# LAN.net
KiCad netlist of a schematic drawn in Altium Designer
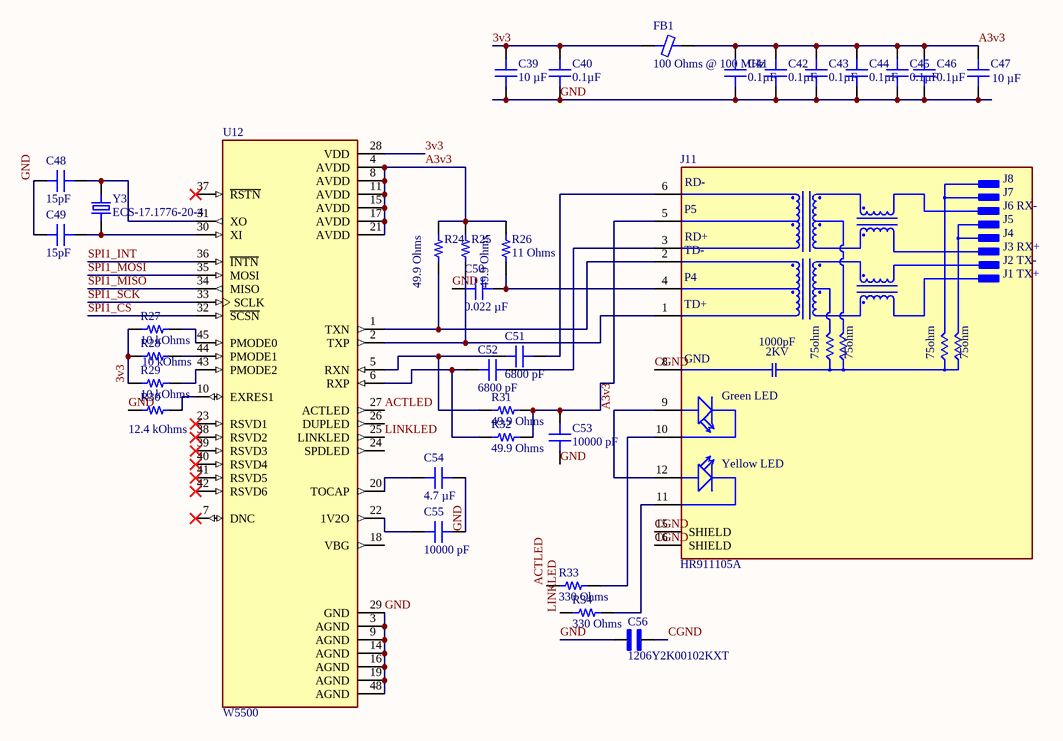
[diagram p0: LAN.SchDoc]

(export (version "E")
  (design (tool "Eeschema 10.0.6"))
  (components
    (comp (ref "C39")
      (value "10 µF")
      (footprint "CAP 1206_3216 - 0.8MM")
      (description "CAP CER 10UF 16V X5R 1206")
      (fields
        (field (name "PART NUMBER") "EMK316BJ106MD-T")
        (field (name "CAPACITANCE") "10 µF")
        (field (name "MANUFACTURER") "Taiyo Yuden")
      )
      (libsource (lib "Celestial Altium Library - altium_library") (part "Capacitor"))
    )
    (comp (ref "C40")
      (value "1µF")
      (footprint "CAP 0805_2012")
      (description "CAP CER 1UF 10V X7R 0805")
      (fields
        (field (name "PART NUMBER") "0805ZC105KAT4A")
        (field (name "CAPACITANCE") "0.1µF")
        (field (name "MANUFACTURER") "AVX Corporation")
      )
      (libsource (lib "Celestial Altium Library - altium_library") (part "Capacitor"))
    )
    (comp (ref "C41")
      (value "1µF")
      (footprint "CAP 0805_2012")
      (description "CAP CER 1UF 10V X7R 0805")
      (fields
        (field (name "PART NUMBER") "0805ZC105KAT4A")
        (field (name "CAPACITANCE") "0.1µF")
        (field (name "MANUFACTURER") "AVX Corporation")
      )
      (libsource (lib "Celestial Altium Library - altium_library") (part "Capacitor"))
    )
    (comp (ref "C42")
      (value "1µF")
      (footprint "CAP 0805_2012")
      (description "CAP CER 1UF 10V X7R 0805")
      (fields
        (field (name "PART NUMBER") "0805ZC105KAT4A")
        (field (name "CAPACITANCE") "0.1µF")
        (field (name "MANUFACTURER") "AVX Corporation")
      )
      (libsource (lib "Celestial Altium Library - altium_library") (part "Capacitor"))
    )
    (comp (ref "C43")
      (value "1µF")
      (footprint "CAP 0805_2012")
      (description "CAP CER 1UF 10V X7R 0805")
      (fields
        (field (name "PART NUMBER") "0805ZC105KAT4A")
        (field (name "CAPACITANCE") "0.1µF")
        (field (name "MANUFACTURER") "AVX Corporation")
      )
      (libsource (lib "Celestial Altium Library - altium_library") (part "Capacitor"))
    )
    (comp (ref "C44")
      (value "1µF")
      (footprint "CAP 0805_2012")
      (description "CAP CER 1UF 10V X7R 0805")
      (fields
        (field (name "PART NUMBER") "0805ZC105KAT4A")
        (field (name "CAPACITANCE") "0.1µF")
        (field (name "MANUFACTURER") "AVX Corporation")
      )
      (libsource (lib "Celestial Altium Library - altium_library") (part "Capacitor"))
    )
    (comp (ref "C45")
      (value "1µF")
      (footprint "CAP 0805_2012")
      (description "CAP CER 1UF 10V X7R 0805")
      (fields
        (field (name "PART NUMBER") "0805ZC105KAT4A")
        (field (name "CAPACITANCE") "0.1µF")
        (field (name "MANUFACTURER") "AVX Corporation")
      )
      (libsource (lib "Celestial Altium Library - altium_library") (part "Capacitor"))
    )
    (comp (ref "C46")
      (value "1µF")
      (footprint "CAP 0805_2012")
      (description "CAP CER 1UF 10V X7R 0805")
      (fields
        (field (name "PART NUMBER") "0805ZC105KAT4A")
        (field (name "CAPACITANCE") "0.1µF")
        (field (name "MANUFACTURER") "AVX Corporation")
      )
      (libsource (lib "Celestial Altium Library - altium_library") (part "Capacitor"))
    )
    (comp (ref "C47")
      (value "10 µF")
      (footprint "CAP 1206_3216 - 0.8MM")
      (description "CAP CER 10UF 16V X5R 1206")
      (fields
        (field (name "PART NUMBER") "EMK316BJ106MD-T")
        (field (name "CAPACITANCE") "10 µF")
        (field (name "MANUFACTURER") "Taiyo Yuden")
      )
      (libsource (lib "Celestial Altium Library - altium_library") (part "Capacitor"))
    )
    (comp (ref "C48")
      (value "15pF")
      (footprint "CAP 0805_2012")
      (description "CAP CER 15PF 50V C0G/NP0 0805")
      (fields
        (field (name "PART NUMBER") "08055A150JAT2A")
        (field (name "CAPACITANCE") "15pF")
        (field (name "MANUFACTURER") "AVX Corporation")
      )
      (libsource (lib "Celestial Altium Library - altium_library") (part "Capacitor"))
    )
    (comp (ref "C49")
      (value "15pF")
      (footprint "CAP 0805_2012")
      (description "CAP CER 15PF 50V C0G/NP0 0805")
      (fields
        (field (name "PART NUMBER") "08055A150JAT2A")
        (field (name "CAPACITANCE") "15pF")
        (field (name "MANUFACTURER") "AVX Corporation")
      )
      (libsource (lib "Celestial Altium Library - altium_library") (part "Capacitor"))
    )
    (comp (ref "C50")
      (value "0.022 µF")
      (footprint "CAP 0805_2012")
      (description "CAP CER 0805 22NF 50V X7R 10%")
      (fields
        (field (name "PART NUMBER") "C0805C223K5RECAUTO")
        (field (name "CAPACITANCE") "0.022 µF")
        (field (name "MANUFACTURER") "KEMET")
      )
      (libsource (lib "Celestial Altium Library - altium_library") (part "Capacitor"))
    )
    (comp (ref "C51")
      (value "6800 pF")
      (footprint "CAP 0805_2012")
      (description "CAP CER 0805 6.8NF 25V C0G 20%")
      (fields
        (field (name "PART NUMBER") "C0805C682M3GEC7800")
        (field (name "CAPACITANCE") "6800 pF")
        (field (name "MANUFACTURER") "KEMET")
      )
      (libsource (lib "Celestial Altium Library - altium_library") (part "Capacitor"))
    )
    (comp (ref "C52")
      (value "6800 pF")
      (footprint "CAP 0805_2012")
      (description "CAP CER 0805 6.8NF 25V C0G 20%")
      (fields
        (field (name "PART NUMBER") "C0805C682M3GEC7800")
        (field (name "CAPACITANCE") "6800 pF")
        (field (name "MANUFACTURER") "KEMET")
      )
      (libsource (lib "Celestial Altium Library - altium_library") (part "Capacitor"))
    )
    (comp (ref "C53")
      (value "10000 pF")
      (footprint "CAP 0805_2012")
      (description "CAP CER 0805 10NF 100V X7R")
      (fields
        (field (name "PART NUMBER") "C0805X103K1RAC3316")
        (field (name "CAPACITANCE") "10000 pF")
        (field (name "MANUFACTURER") "KEMET")
      )
      (libsource (lib "Celestial Altium Library - altium_library") (part "Capacitor"))
    )
    (comp (ref "C54")
      (value "4.7 µF")
      (footprint "CAP 0805_2012")
      (description "4.70UF 25.0V")
      (fields
        (field (name "PART NUMBER") "C0805X475M3RAC7800")
        (field (name "CAPACITANCE") "4.7 µF")
        (field (name "MANUFACTURER") "KEMET")
      )
      (libsource (lib "Celestial Altium Library - altium_library") (part "Capacitor"))
    )
    (comp (ref "C55")
      (value "10000 pF")
      (footprint "CAP 0805_2012")
      (description "CAP CER 0805 10NF 100V X7R")
      (fields
        (field (name "PART NUMBER") "C0805X103K1RAC3316")
        (field (name "CAPACITANCE") "10000 pF")
        (field (name "MANUFACTURER") "KEMET")
      )
      (libsource (lib "Celestial Altium Library - altium_library") (part "Capacitor"))
    )
    (comp (ref "C56")
      (value "1206Y2K00102KXT")
      (footprint "CAPC3216X160N")
      (description "1000 pF Â±10% 2000V (2kV) Ceramic Capacitor X7R 1206 (3216 Metric)")
      (fields (field (name "MF") "Knowles Syfer"))
      (libsource (lib "1206Y2K00102KXT") (part "1206Y2K00102KXT"))
    )
    (comp (ref "FB1")
      (value "100 Ohms @ 100 MHz")
      (footprint "FER 0805_2012")
      (description "FERRITE BEAD, CHIP, 0805, 100 OH")
      (fields (field (name "PART NUMBER") "HRB0805S101K1.00FT") (field (name "MANUFACTURER") "AEM, Inc."))
      (libsource (lib "Celestial Altium Library - altium_library") (part "Ferrite Chip"))
    )
    (comp (ref "J11")
      (value "HR911105A")
      (footprint "HANRUN_HR911105A")
      (description "DIP RJ45 Connector;")
      (fields (field (name "MF") "hanrun"))
      (libsource (lib "HR911105A") (part "HR911105A"))
    )
    (comp (ref "R24")
      (value "49.9 Ohms")
      (footprint "RES 0805_2012")
      (description "RCC0805 100 49R9 1% ET1 E3")
      (fields (field (name "PART NUMBER") "RCC080549R9FKEA") (field (name "MANUFACTURER") "Vishay Dale"))
      (libsource (lib "Celestial Altium Library - altium_library") (part "Resistor"))
    )
    (comp (ref "R25")
      (value "49.9 Ohms")
      (footprint "RES 0805_2012")
      (description "RCC0805 100 49R9 1% ET1 E3")
      (fields (field (name "PART NUMBER") "RCC080549R9FKEA") (field (name "MANUFACTURER") "Vishay Dale"))
      (libsource (lib "Celestial Altium Library - altium_library") (part "Resistor"))
    )
    (comp (ref "R26")
      (value "11 Ohms")
      (footprint "RES 0805_2012")
      (description "RES SMD 11 OHM 1% 1/8W 0805")
      (fields (field (name "PART NUMBER") "KTR10EZPF11R0") (field (name "MANUFACTURER") "Rohm Semiconductor"))
      (libsource (lib "Celestial Altium Library - altium_library") (part "Resistor"))
    )
    (comp (ref "R27")
      (value "10 kOhms")
      (footprint "RES 0805_2012")
      (description "RES 10K OHM 0.1% 1/10W 0805")
      (fields
        (field (name "PART NUMBER") "RNCS0805BKE10K0")
        (field (name "MANUFACTURER") "Stackpole Electronics Inc")
      )
      (libsource (lib "Celestial Altium Library - altium_library") (part "Resistor"))
    )
    (comp (ref "R28")
      (value "10 kOhms")
      (footprint "RES 0805_2012")
      (description "RES 10K OHM 0.1% 1/10W 0805")
      (fields
        (field (name "PART NUMBER") "RNCS0805BKE10K0")
        (field (name "MANUFACTURER") "Stackpole Electronics Inc")
      )
      (libsource (lib "Celestial Altium Library - altium_library") (part "Resistor"))
    )
    (comp (ref "R29")
      (value "10 kOhms")
      (footprint "RES 0805_2012")
      (description "RES 10K OHM 0.1% 1/10W 0805")
      (fields
        (field (name "PART NUMBER") "RNCS0805BKE10K0")
        (field (name "MANUFACTURER") "Stackpole Electronics Inc")
      )
      (libsource (lib "Celestial Altium Library - altium_library") (part "Resistor"))
    )
    (comp (ref "R30")
      (value "12.4 kOhms")
      (footprint "RES 0805_2012")
      (description "RES 12.4 KOHMS 0.1% 1/5W 0805")
      (fields
        (field (name "PART NUMBER") "RQ73C2A12K4BTD")
        (field (name "MANUFACTURER") "TE Connectivity Passive Product")
      )
      (libsource (lib "Celestial Altium Library - altium_library") (part "Resistor"))
    )
    (comp (ref "R31")
      (value "49.9 Ohms")
      (footprint "RES 0805_2012")
      (description "RCC0805 100 49R9 1% ET1 E3")
      (fields (field (name "PART NUMBER") "RCC080549R9FKEA") (field (name "MANUFACTURER") "Vishay Dale"))
      (libsource (lib "Celestial Altium Library - altium_library") (part "Resistor"))
    )
    (comp (ref "R32")
      (value "49.9 Ohms")
      (footprint "RES 0805_2012")
      (description "RCC0805 100 49R9 1% ET1 E3")
      (fields (field (name "PART NUMBER") "RCC080549R9FKEA") (field (name "MANUFACTURER") "Vishay Dale"))
      (libsource (lib "Celestial Altium Library - altium_library") (part "Resistor"))
    )
    (comp (ref "R33")
      (value "330 Ohms")
      (footprint "YAGEO RES 0805_2012")
      (description "RES 330 OHM 1% 1/8W 0805")
      (fields (field (name "PART NUMBER") "RC0805FR-07330RL") (field (name "MANUFACTURER") "Yageo"))
      (libsource (lib "Celestial Altium Library - altium_library") (part "Resistor"))
    )
    (comp (ref "R34")
      (value "330 Ohms")
      (footprint "YAGEO RES 0805_2012")
      (description "RES 330 OHM 1% 1/8W 0805")
      (fields (field (name "PART NUMBER") "RC0805FR-07330RL") (field (name "MANUFACTURER") "Yageo"))
      (libsource (lib "Celestial Altium Library - altium_library") (part "Resistor"))
    )
    (comp (ref "U12")
      (value "W5500")
      (footprint "QFP50P900X900X160-48N")
      (description "Hardwired TCP/IP embedded Ethernet controller")
      (libsource (lib "W5500") (part "W5500"))
    )
    (comp (ref "Y3")
      (value "ECS-17.1776-20-4")
      (footprint "XTAL_ECS-160-20-4X")
      (description "Crystals 17.1776MHz HC49S")
      (fields (field (name "MF") "ECS International"))
      (libsource (lib "ECS-17.1776-20-4") (part "ECS-17.1776-20-4"))
    )
  )
  (nets
    (net (code "1") (name "/3v3") (class "Default")
      (node (ref "C39") (pin "2") (pinfunction "2_2") (pintype "passive"))
      (node (ref "C40") (pin "2") (pinfunction "2_2") (pintype "passive"))
      (node (ref "FB1") (pin "1") (pinfunction "1_1") (pintype "passive"))
      (node (ref "R27") (pin "1") (pinfunction "1_1") (pintype "passive"))
      (node (ref "R28") (pin "1") (pinfunction "1_1") (pintype "passive"))
      (node (ref "R29") (pin "1") (pinfunction "1_1") (pintype "passive"))
      (node (ref "U12") (pin "28") (pinfunction "VDD_28") (pintype "power_in"))
    )
    (net (code "2") (name "/A3v3") (class "Default")
      (node (ref "C41") (pin "2") (pinfunction "2_2") (pintype "passive"))
      (node (ref "C42") (pin "2") (pinfunction "2_2") (pintype "passive"))
      (node (ref "C43") (pin "2") (pinfunction "2_2") (pintype "passive"))
      (node (ref "C44") (pin "2") (pinfunction "2_2") (pintype "passive"))
      (node (ref "C45") (pin "2") (pinfunction "2_2") (pintype "passive"))
      (node (ref "C46") (pin "2") (pinfunction "2_2") (pintype "passive"))
      (node (ref "C47") (pin "2") (pinfunction "2_2") (pintype "passive"))
      (node (ref "FB1") (pin "2") (pinfunction "2_2") (pintype "passive"))
      (node (ref "J11") (pin "12") (pinfunction "YA_12") (pintype "passive"))
      (node (ref "J11") (pin "9") (pinfunction "GA_9") (pintype "passive"))
      (node (ref "R24") (pin "2") (pinfunction "2_2") (pintype "passive"))
      (node (ref "R25") (pin "2") (pinfunction "2_2") (pintype "passive"))
      (node (ref "R26") (pin "2") (pinfunction "2_2") (pintype "passive"))
      (node (ref "U12") (pin "11") (pinfunction "AVDD_11") (pintype "power_in"))
      (node (ref "U12") (pin "15") (pinfunction "AVDD_15") (pintype "power_in"))
      (node (ref "U12") (pin "17") (pinfunction "AVDD_17") (pintype "power_in"))
      (node (ref "U12") (pin "21") (pinfunction "AVDD_21") (pintype "power_in"))
      (node (ref "U12") (pin "4") (pinfunction "AVDD_4") (pintype "power_in"))
      (node (ref "U12") (pin "8") (pinfunction "AVDD_8") (pintype "power_in"))
    )
    (net (code "3") (name "/ACTLED") (class "Default")
      (node (ref "R33") (pin "1") (pinfunction "1_1") (pintype "passive"))
      (node (ref "U12") (pin "27") (pinfunction "ACTLED_27") (pintype "output"))
    )
    (net (code "4") (name "/CGND") (class "Default")
      (node (ref "C56") (pin "2") (pinfunction "2_2") (pintype "passive"))
      (node (ref "J11") (pin "15") (pinfunction "SHIELD_15") (pintype "passive"))
      (node (ref "J11") (pin "16") (pinfunction "SHIELD_16") (pintype "passive"))
      (node (ref "J11") (pin "8") (pinfunction "GND_8") (pintype "power_in"))
    )
    (net (code "5") (name "/GND") (class "Default")
      (node (ref "C39") (pin "1") (pinfunction "1_1") (pintype "passive"))
      (node (ref "C40") (pin "1") (pinfunction "1_1") (pintype "passive"))
      (node (ref "C41") (pin "1") (pinfunction "1_1") (pintype "passive"))
      (node (ref "C42") (pin "1") (pinfunction "1_1") (pintype "passive"))
      (node (ref "C43") (pin "1") (pinfunction "1_1") (pintype "passive"))
      (node (ref "C44") (pin "1") (pinfunction "1_1") (pintype "passive"))
      (node (ref "C45") (pin "1") (pinfunction "1_1") (pintype "passive"))
      (node (ref "C46") (pin "1") (pinfunction "1_1") (pintype "passive"))
      (node (ref "C47") (pin "1") (pinfunction "1_1") (pintype "passive"))
      (node (ref "C48") (pin "1") (pinfunction "1_1") (pintype "passive"))
      (node (ref "C49") (pin "1") (pinfunction "1_1") (pintype "passive"))
      (node (ref "C50") (pin "2") (pinfunction "2_2") (pintype "passive"))
      (node (ref "C53") (pin "1") (pinfunction "1_1") (pintype "passive"))
      (node (ref "C54") (pin "2") (pinfunction "2_2") (pintype "passive"))
      (node (ref "C55") (pin "2") (pinfunction "2_2") (pintype "passive"))
      (node (ref "C56") (pin "1") (pinfunction "1_1") (pintype "passive"))
      (node (ref "R30") (pin "1") (pinfunction "1_1") (pintype "passive"))
      (node (ref "U12") (pin "14") (pinfunction "AGND_14") (pintype "power_in"))
      (node (ref "U12") (pin "16") (pinfunction "AGND_16") (pintype "power_in"))
      (node (ref "U12") (pin "19") (pinfunction "AGND_19") (pintype "power_in"))
      (node (ref "U12") (pin "29") (pinfunction "GND_29") (pintype "passive"))
      (node (ref "U12") (pin "3") (pinfunction "AGND_3") (pintype "power_in"))
      (node (ref "U12") (pin "48") (pinfunction "AGND_48") (pintype "power_in"))
      (node (ref "U12") (pin "9") (pinfunction "AGND_9") (pintype "power_in"))
    )
    (net (code "6") (name "/LINKLED") (class "Default")
      (node (ref "R34") (pin "1") (pinfunction "1_1") (pintype "passive"))
      (node (ref "U12") (pin "25") (pinfunction "LINKLED_25") (pintype "output"))
    )
    (net (code "7") (name "/SPI1_CS") (class "Default")
      (node (ref "U12") (pin "32") (pinfunction "~{SCSN}_32") (pintype "input"))
    )
    (net (code "8") (name "/SPI1_INT") (class "Default")
      (node (ref "U12") (pin "36") (pinfunction "~{INTN}_36") (pintype "input"))
    )
    (net (code "9") (name "/SPI1_MISO") (class "Default")
      (node (ref "U12") (pin "34") (pinfunction "MISO_34") (pintype "output"))
    )
    (net (code "10") (name "/SPI1_MOSI") (class "Default")
      (node (ref "U12") (pin "35") (pinfunction "MOSI_35") (pintype "input"))
    )
    (net (code "11") (name "/SPI1_SCK") (class "Default")
      (node (ref "U12") (pin "33") (pinfunction "SCLK_33") (pintype "input"))
    )
    (net (code "12") (name "Net-(J11-GC)") (class "Default")
      (node (ref "J11") (pin "10") (pinfunction "GC_10") (pintype "passive"))
      (node (ref "R33") (pin "2") (pinfunction "2_2") (pintype "passive"))
    )
    (net (code "13") (name "Net-(J11-P4)") (class "Default")
      (node (ref "C50") (pin "1") (pinfunction "1_1") (pintype "passive"))
      (node (ref "J11") (pin "4") (pinfunction "P4_4") (pintype "passive"))
      (node (ref "R26") (pin "1") (pinfunction "1_1") (pintype "passive"))
    )
    (net (code "14") (name "Net-(J11-P5)") (class "Default")
      (node (ref "C53") (pin "2") (pinfunction "2_2") (pintype "passive"))
      (node (ref "J11") (pin "5") (pinfunction "P5_5") (pintype "passive"))
      (node (ref "R31") (pin "1") (pinfunction "1_1") (pintype "passive"))
      (node (ref "R32") (pin "1") (pinfunction "1_1") (pintype "passive"))
    )
    (net (code "15") (name "Net-(J11-RD+)") (class "Default")
      (node (ref "C52") (pin "2") (pinfunction "2_2") (pintype "passive"))
      (node (ref "J11") (pin "3") (pinfunction "RD+_3") (pintype "passive"))
    )
    (net (code "16") (name "Net-(J11-RD-)") (class "Default")
      (node (ref "C51") (pin "2") (pinfunction "2_2") (pintype "passive"))
      (node (ref "J11") (pin "6") (pinfunction "RD-_6") (pintype "passive"))
    )
    (net (code "17") (name "Net-(J11-TD+)") (class "Default")
      (node (ref "J11") (pin "1") (pinfunction "TD+_1") (pintype "passive"))
      (node (ref "R25") (pin "1") (pinfunction "1_1") (pintype "passive"))
      (node (ref "U12") (pin "2") (pinfunction "TXP_2") (pintype "output"))
    )
    (net (code "18") (name "Net-(J11-TD-)") (class "Default")
      (node (ref "J11") (pin "2") (pinfunction "TD-_2") (pintype "passive"))
      (node (ref "R24") (pin "1") (pinfunction "1_1") (pintype "passive"))
      (node (ref "U12") (pin "1") (pinfunction "TXN_1") (pintype "output"))
    )
    (net (code "19") (name "Net-(J11-YC)") (class "Default")
      (node (ref "J11") (pin "11") (pinfunction "YC_11") (pintype "passive"))
      (node (ref "R34") (pin "2") (pinfunction "2_2") (pintype "passive"))
    )
    (net (code "20") (name "Net-(U12-1V2O)") (class "Default")
      (node (ref "C55") (pin "1") (pinfunction "1_1") (pintype "passive"))
      (node (ref "U12") (pin "22") (pinfunction "1V2O_22") (pintype "output"))
    )
    (net (code "21") (name "Net-(U12-EXRES1)") (class "Default")
      (node (ref "R30") (pin "2") (pinfunction "2_2") (pintype "passive"))
      (node (ref "U12") (pin "10") (pinfunction "EXRES1_10") (pintype "bidirectional"))
    )
    (net (code "22") (name "Net-(U12-PMODE0)") (class "Default")
      (node (ref "R27") (pin "2") (pinfunction "2_2") (pintype "passive"))
      (node (ref "U12") (pin "45") (pinfunction "PMODE0_45") (pintype "input"))
    )
    (net (code "23") (name "Net-(U12-PMODE1)") (class "Default")
      (node (ref "R28") (pin "2") (pinfunction "2_2") (pintype "passive"))
      (node (ref "U12") (pin "44") (pinfunction "PMODE1_44") (pintype "input"))
    )
    (net (code "24") (name "Net-(U12-PMODE2)") (class "Default")
      (node (ref "R29") (pin "2") (pinfunction "2_2") (pintype "passive"))
      (node (ref "U12") (pin "43") (pinfunction "PMODE2_43") (pintype "input"))
    )
    (net (code "25") (name "Net-(U12-RXN)") (class "Default")
      (node (ref "C51") (pin "1") (pinfunction "1_1") (pintype "passive"))
      (node (ref "R31") (pin "2") (pinfunction "2_2") (pintype "passive"))
      (node (ref "U12") (pin "5") (pinfunction "RXN_5") (pintype "input"))
    )
    (net (code "26") (name "Net-(U12-RXP)") (class "Default")
      (node (ref "C52") (pin "1") (pinfunction "1_1") (pintype "passive"))
      (node (ref "R32") (pin "2") (pinfunction "2_2") (pintype "passive"))
      (node (ref "U12") (pin "6") (pinfunction "RXP_6") (pintype "input"))
    )
    (net (code "27") (name "Net-(U12-TOCAP)") (class "Default")
      (node (ref "C54") (pin "1") (pinfunction "1_1") (pintype "passive"))
      (node (ref "U12") (pin "20") (pinfunction "TOCAP_20") (pintype "output"))
    )
    (net (code "28") (name "Net-(U12-XI)") (class "Default")
      (node (ref "C49") (pin "2") (pinfunction "2_2") (pintype "passive"))
      (node (ref "U12") (pin "30") (pinfunction "XI_30") (pintype "input"))
      (node (ref "Y3") (pin "1") (pinfunction "1_1") (pintype "passive"))
    )
    (net (code "29") (name "Net-(U12-XO)") (class "Default")
      (node (ref "C48") (pin "2") (pinfunction "2_2") (pintype "passive"))
      (node (ref "U12") (pin "31") (pinfunction "XO_31") (pintype "output"))
      (node (ref "Y3") (pin "2") (pinfunction "2_2") (pintype "passive"))
    )
    (net (code "30") (name "unconnected-(U12-DNC-Pad7)") (class "Default")
      (node (ref "U12") (pin "7") (pinfunction "DNC_7") (pintype "bidirectional+no_connect"))
    )
    (net (code "31") (name "unconnected-(U12-DUPLED-Pad26)") (class "Default")
      (node (ref "U12") (pin "26") (pinfunction "DUPLED_26") (pintype "output"))
    )
    (net (code "32") (name "unconnected-(U12-RSVD1-Pad23)") (class "Default")
      (node (ref "U12") (pin "23") (pinfunction "RSVD1_23") (pintype "input+no_connect"))
    )
    (net (code "33") (name "unconnected-(U12-RSVD2-Pad38)") (class "Default")
      (node (ref "U12") (pin "38") (pinfunction "RSVD2_38") (pintype "input+no_connect"))
    )
    (net (code "34") (name "unconnected-(U12-RSVD3-Pad39)") (class "Default")
      (node (ref "U12") (pin "39") (pinfunction "RSVD3_39") (pintype "input+no_connect"))
    )
    (net (code "35") (name "unconnected-(U12-RSVD4-Pad40)") (class "Default")
      (node (ref "U12") (pin "40") (pinfunction "RSVD4_40") (pintype "input+no_connect"))
    )
    (net (code "36") (name "unconnected-(U12-RSVD5-Pad41)") (class "Default")
      (node (ref "U12") (pin "41") (pinfunction "RSVD5_41") (pintype "input+no_connect"))
    )
    (net (code "37") (name "unconnected-(U12-RSVD6-Pad42)") (class "Default")
      (node (ref "U12") (pin "42") (pinfunction "RSVD6_42") (pintype "input+no_connect"))
    )
    (net (code "38") (name "unconnected-(U12-SPDLED-Pad24)") (class "Default")
      (node (ref "U12") (pin "24") (pinfunction "SPDLED_24") (pintype "output"))
    )
    (net (code "39") (name "unconnected-(U12-VBG-Pad18)") (class "Default")
      (node (ref "U12") (pin "18") (pinfunction "VBG_18") (pintype "output"))
    )
    (net (code "40") (name "unconnected-(U12-~{RSTN}-Pad37)") (class "Default")
      (node (ref "U12") (pin "37") (pinfunction "~{RSTN}_37") (pintype "input+no_connect"))
    )
  )
)
